# RP2040_Extender.net
KiCad netlist of a schematic drawn in Altium Designer
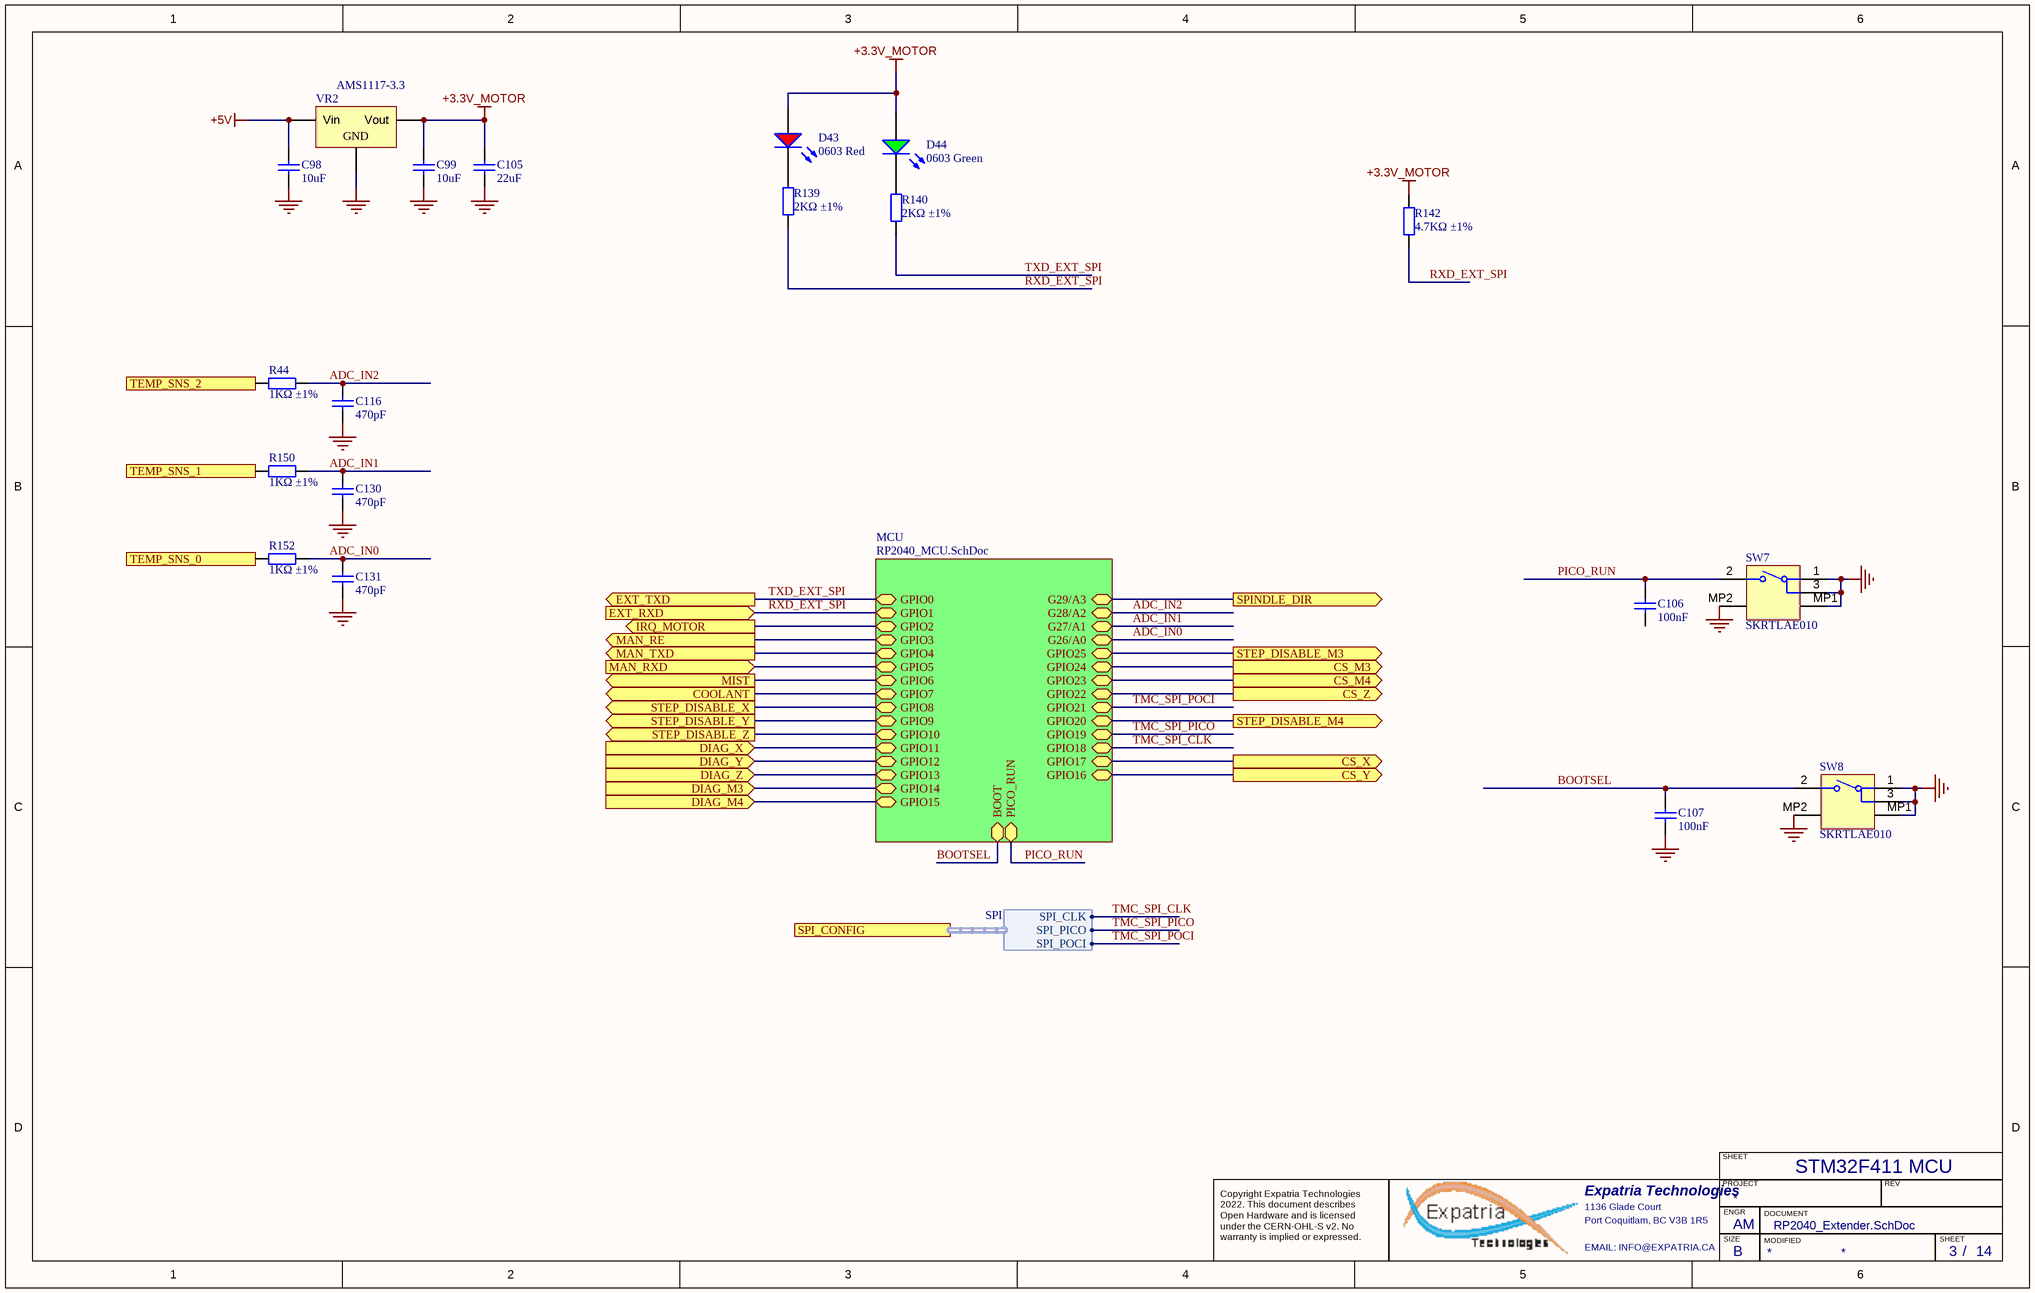
[diagram p0: RP2040_Extender.SchDoc]

(export (version "E")
  (design (tool "Eeschema 10.0.6"))
  (components
    (comp (ref "C98")
      (value "10uF")
      (footprint "1206_C")
      (description "Chip capacitors")
      (fields
        (field (name "MANUFACTURER") "Samsung Electro-Mechanics")
        (field (name "PARTNUMBER") "CL31A106KBHNNNE")
      )
      (libsource (lib "Cap") (part "1206 10uF (106) 10% 50V"))
    )
    (comp (ref "C99")
      (value "10uF")
      (footprint "1206_C")
      (description "Chip capacitors")
      (fields
        (field (name "MANUFACTURER") "Samsung Electro-Mechanics")
        (field (name "PARTNUMBER") "CL31A106KBHNNNE")
      )
      (libsource (lib "Cap") (part "1206 10uF (106) 10% 50V"))
    )
    (comp (ref "C105")
      (value "22uF")
      (footprint "0805_C")
      (description "Chip capacitors")
      (fields
        (field (name "MANUFACTURER") "Samsung Electro-Mechanics")
        (field (name "PARTNUMBER") "CL21A226MAQNNNE")
      )
      (libsource (lib "Cap") (part "0805 22uF (226) 20% 25V"))
    )
    (comp (ref "C106")
      (value "100nF")
      (footprint "0402_C")
      (description "Chip capacitors")
      (fields
        (field (name "MANUFACTURER") "Samsung Electro-Mechanics")
        (field (name "PARTNUMBER") "CL05B104KO5NNNC")
      )
      (libsource (lib "Cap") (part "0402 100nF (104) 10% 16V"))
    )
    (comp (ref "C107")
      (value "100nF")
      (footprint "0402_C")
      (description "Chip capacitors")
      (fields
        (field (name "MANUFACTURER") "Samsung Electro-Mechanics")
        (field (name "PARTNUMBER") "CL05B104KO5NNNC")
      )
      (libsource (lib "Cap") (part "0402 100nF (104) 10% 16V"))
    )
    (comp (ref "C116")
      (value "470pF")
      (footprint "0603_C")
      (description "Chip capacitors")
      (fields
        (field (name "MANUFACTURER") "Guangdong Fenghua Advanced Tech")
        (field (name "PARTNUMBER") "0603B471K500NT")
      )
      (libsource (lib "Cap") (part "0603 470pF (471) 10% 50V"))
    )
    (comp (ref "C130")
      (value "470pF")
      (footprint "0603_C")
      (description "Chip capacitors")
      (fields
        (field (name "MANUFACTURER") "Guangdong Fenghua Advanced Tech")
        (field (name "PARTNUMBER") "0603B471K500NT")
      )
      (libsource (lib "Cap") (part "0603 470pF (471) 10% 50V"))
    )
    (comp (ref "C131")
      (value "470pF")
      (footprint "0603_C")
      (description "Chip capacitors")
      (fields
        (field (name "MANUFACTURER") "Guangdong Fenghua Advanced Tech")
        (field (name "PARTNUMBER") "0603B471K500NT")
      )
      (libsource (lib "Cap") (part "0603 470pF (471) 10% 50V"))
    )
    (comp (ref "D43")
      (value "0603 Red")
      (footprint "0603_LED_S1")
      (description "LED")
      (libsource (lib "LED") (part "0603 LED Red"))
    )
    (comp (ref "D44")
      (value "0603 Green")
      (footprint "0603_LED_S1")
      (description "LED")
      (libsource (lib "LED") (part "0603 LED Green"))
    )
    (comp (ref "R44")
      (value "1KΩ ±1%")
      (footprint "0603_R")
      (description "Chip resistor")
      (fields (field (name "MANUFACTURER") "Uniroyal Elec") (field (name "PARTNUMBER") "0603WAF1001T5E"))
      (libsource (lib "RES") (part "0603 1K (1001) 1%"))
    )
    (comp (ref "R139")
      (value "2KΩ ±1%")
      (footprint "0603_R")
      (description "Chip resistor")
      (fields (field (name "MANUFACTURER") "Uniroyal Elec") (field (name "PARTNUMBER") "0603WAF2001T5E"))
      (libsource (lib "RES") (part "0603 2K (2001) 1%"))
    )
    (comp (ref "R140")
      (value "2KΩ ±1%")
      (footprint "0603_R")
      (description "Chip resistor")
      (fields (field (name "MANUFACTURER") "Uniroyal Elec") (field (name "PARTNUMBER") "0603WAF2001T5E"))
      (libsource (lib "RES") (part "0603 2K (2001) 1%"))
    )
    (comp (ref "R142")
      (value "4.7KΩ ±1%")
      (footprint "0603_R")
      (description "Chip resistor")
      (fields (field (name "MANUFACTURER") "Uniroyal Elec") (field (name "PARTNUMBER") "0603WAF4701T5E"))
      (libsource (lib "RES") (part "0603 4.7K (4701) 1%"))
    )
    (comp (ref "R150")
      (value "1KΩ ±1%")
      (footprint "0603_R")
      (description "Chip resistor")
      (fields (field (name "MANUFACTURER") "Uniroyal Elec") (field (name "PARTNUMBER") "0603WAF1001T5E"))
      (libsource (lib "RES") (part "0603 1K (1001) 1%"))
    )
    (comp (ref "R152")
      (value "1KΩ ±1%")
      (footprint "0603_R")
      (description "Chip resistor")
      (fields (field (name "MANUFACTURER") "Uniroyal Elec") (field (name "PARTNUMBER") "0603WAF1001T5E"))
      (libsource (lib "RES") (part "0603 1K (1001) 1%"))
    )
    (comp (ref "SW7")
      (value "SKRTLAE010")
      (footprint "ALPS-SKRTLAE010_V")
      (description "Side Push Type, 250 V, -40 to 90 degC, 3-Pin SMD, RoHS, Tape and Reel")
      (fields (field (name "MANUFACTURER") "ALPS"))
      (libsource (lib "Altium Content Vault") (part "SW_SPST-3_A"))
    )
    (comp (ref "SW8")
      (value "SKRTLAE010")
      (footprint "ALPS-SKRTLAE010_V")
      (description "Side Push Type, 250 V, -40 to 90 degC, 3-Pin SMD, RoHS, Tape and Reel")
      (fields (field (name "MANUFACTURER") "ALPS"))
      (libsource (lib "Altium Content Vault") (part "SW_SPST-3_A"))
    )
    (comp (ref "VR2")
      (value "AMS1117-3.3")
      (footprint "SOT-223")
      (description "Vout=3.3V 1A 72dB@(120Hz) (LDO)")
      (libsource (lib "LDO") (part "SOT-223 AMS1117-3.3"))
    )
  )
  (nets
    (net (code "2") (name "+3.3V_MOTOR") (class "Default")
      (node (ref "C105") (pin "2") (pinfunction "2_2") (pintype "passive"))
      (node (ref "C99") (pin "2") (pinfunction "2_2") (pintype "passive"))
      (node (ref "D43") (pin "A") (pinfunction "A_A") (pintype "passive"))
      (node (ref "D44") (pin "A") (pinfunction "A_A") (pintype "passive"))
      (node (ref "R142") (pin "2") (pinfunction "2_2") (pintype "passive"))
      (node (ref "VR2") (pin "2") (pinfunction "Vout_2") (pintype "passive"))
    )
    (net (code "3") (name "+5V") (class "Default")
      (node (ref "C98") (pin "2") (pinfunction "2_2") (pintype "passive"))
      (node (ref "VR2") (pin "3") (pinfunction "Vin_3") (pintype "passive"))
    )
    (net (code "4") (name "/ADC_IN0") (class "Default")
      (node (ref "C131") (pin "2") (pinfunction "2_2") (pintype "passive"))
      (node (ref "R152") (pin "2") (pinfunction "2_2") (pintype "passive"))
    )
    (net (code "5") (name "/ADC_IN1") (class "Default")
      (node (ref "C130") (pin "2") (pinfunction "2_2") (pintype "passive"))
      (node (ref "R150") (pin "2") (pinfunction "2_2") (pintype "passive"))
    )
    (net (code "6") (name "/ADC_IN2") (class "Default")
      (node (ref "C116") (pin "2") (pinfunction "2_2") (pintype "passive"))
      (node (ref "R44") (pin "2") (pinfunction "2_2") (pintype "passive"))
    )
    (net (code "7") (name "/BOOTSEL") (class "Default")
      (node (ref "C107") (pin "2") (pinfunction "2_2") (pintype "passive"))
      (node (ref "SW8") (pin "2") (pinfunction "2_2") (pintype "passive"))
    )
    (net (code "24") (name "/PICO_RUN") (class "Default")
      (node (ref "C106") (pin "2") (pinfunction "2_2") (pintype "passive"))
      (node (ref "SW7") (pin "2") (pinfunction "2_2") (pintype "passive"))
    )
    (net (code "25") (name "/RXD_EXT_SPI") (class "Default")
      (node (ref "R139") (pin "1") (pinfunction "1_1") (pintype "passive"))
      (node (ref "R142") (pin "1") (pinfunction "1_1") (pintype "passive"))
    )
    (net (code "32") (name "/TEMP_SNS_0") (class "Default")
      (node (ref "R152") (pin "1") (pinfunction "1_1") (pintype "passive"))
    )
    (net (code "33") (name "/TEMP_SNS_1") (class "Default")
      (node (ref "R150") (pin "1") (pinfunction "1_1") (pintype "passive"))
    )
    (net (code "34") (name "/TEMP_SNS_2") (class "Default")
      (node (ref "R44") (pin "1") (pinfunction "1_1") (pintype "passive"))
    )
    (net (code "38") (name "/TXD_EXT_SPI") (class "Default")
      (node (ref "R140") (pin "1") (pinfunction "1_1") (pintype "passive"))
    )
    (net (code "40") (name "GND") (class "Default")
      (node (ref "C105") (pin "1") (pinfunction "1_1") (pintype "passive"))
      (node (ref "C107") (pin "1") (pinfunction "1_1") (pintype "passive"))
      (node (ref "C116") (pin "1") (pinfunction "1_1") (pintype "passive"))
      (node (ref "C130") (pin "1") (pinfunction "1_1") (pintype "passive"))
      (node (ref "C131") (pin "1") (pinfunction "1_1") (pintype "passive"))
      (node (ref "C98") (pin "1") (pinfunction "1_1") (pintype "passive"))
      (node (ref "C99") (pin "1") (pinfunction "1_1") (pintype "passive"))
      (node (ref "SW7") (pin "1") (pinfunction "1_1") (pintype "passive"))
      (node (ref "SW7") (pin "3") (pinfunction "3_3") (pintype "passive"))
      (node (ref "SW7") (pin "MP1") (pinfunction "MP1_MP1") (pintype "passive"))
      (node (ref "SW7") (pin "MP2") (pinfunction "MP2_MP2") (pintype "passive"))
      (node (ref "SW8") (pin "1") (pinfunction "1_1") (pintype "passive"))
      (node (ref "SW8") (pin "3") (pinfunction "3_3") (pintype "passive"))
      (node (ref "SW8") (pin "MP1") (pinfunction "MP1_MP1") (pintype "passive"))
      (node (ref "SW8") (pin "MP2") (pinfunction "MP2_MP2") (pintype "passive"))
      (node (ref "VR2") (pin "1") (pinfunction "GND_1") (pintype "passive"))
    )
    (net (code "41") (name "Net-(D43-PadK)") (class "Default")
      (node (ref "D43") (pin "K") (pinfunction "K_K") (pintype "passive"))
      (node (ref "R139") (pin "2") (pinfunction "2_2") (pintype "passive"))
    )
    (net (code "42") (name "Net-(D44-PadK)") (class "Default")
      (node (ref "D44") (pin "K") (pinfunction "K_K") (pintype "passive"))
      (node (ref "R140") (pin "2") (pinfunction "2_2") (pintype "passive"))
    )
    (net (code "43") (name "unconnected-(C106-Pad1)") (class "Default")
      (node (ref "C106") (pin "1") (pinfunction "1_1") (pintype "passive"))
    )
  )
)
